# resisitive_pos_servo2.net
KiCad netlist of a schematic drawn in EAGLE
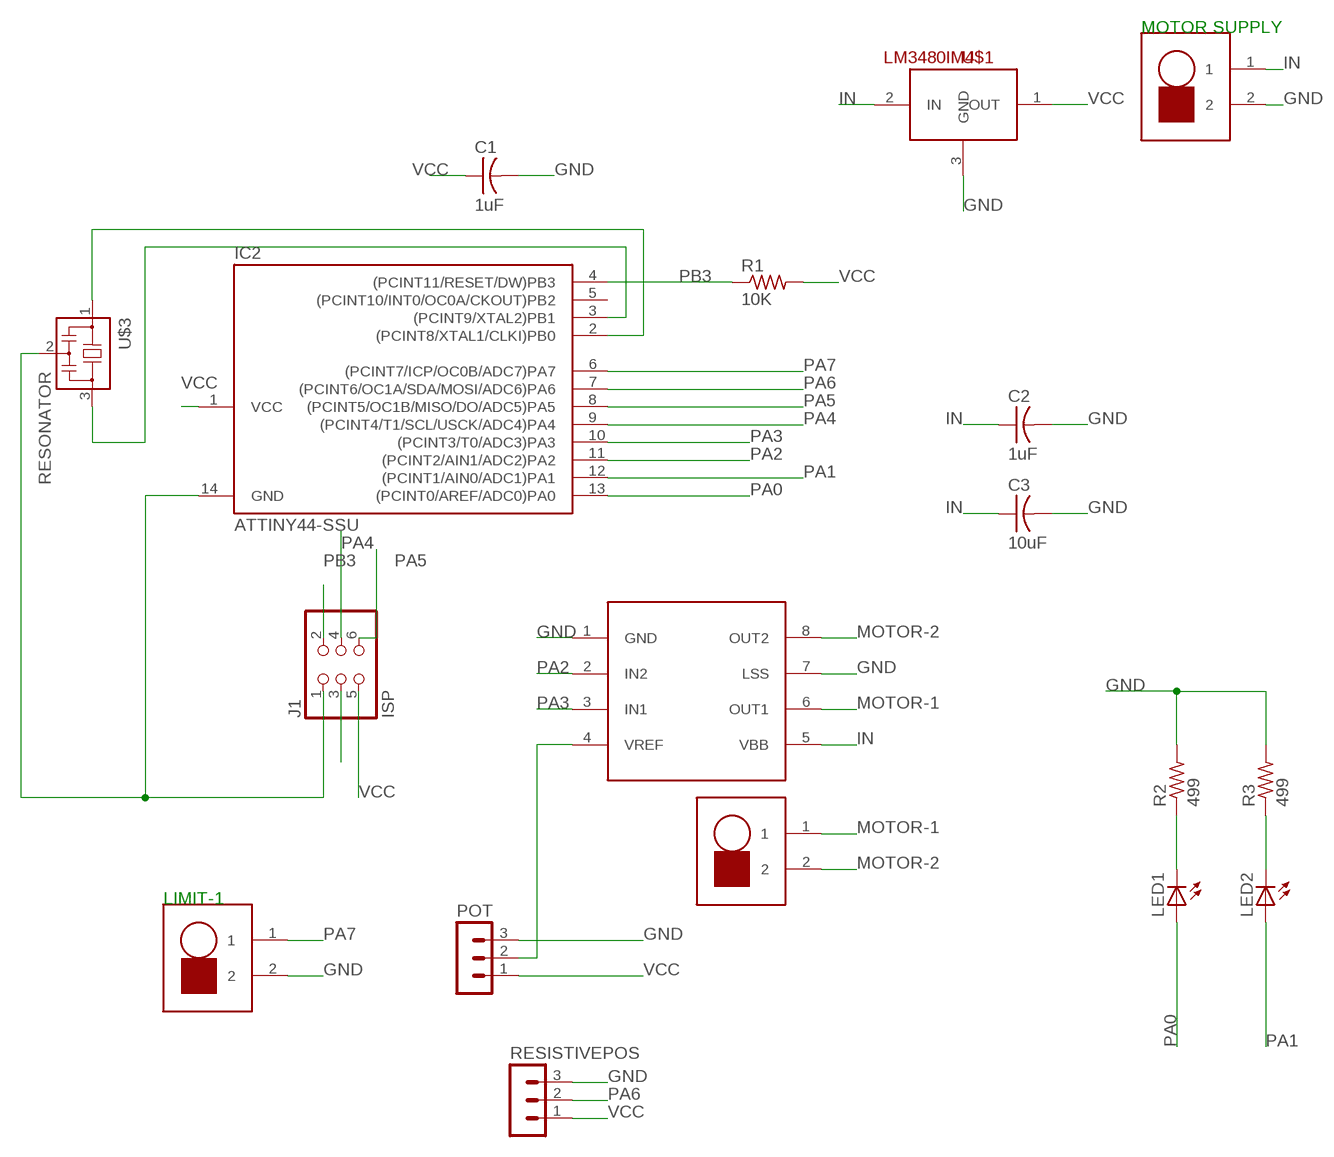
[diagram p0: schematic, sheet 1]

(export (version "E")
  (design (tool "Eeschema 10.0.6"))
  (components
    (comp (ref "C1")
      (value "1uF")
      (footprint "eagle-import:C1206")
      (libsource (lib "eagle-import") (part "CAP-US1206"))
    )
    (comp (ref "C2")
      (value "1uF")
      (footprint "eagle-import:C1206")
      (libsource (lib "eagle-import") (part "CAP-US1206"))
    )
    (comp (ref "C3")
      (value "10uF")
      (footprint "eagle-import:C1206")
      (libsource (lib "eagle-import") (part "CAP-US1206"))
    )
    (comp (ref "IC2")
      (value "ATTINY44-SSU")
      (footprint "eagle-import:SOIC14")
      (libsource (lib "eagle-import") (part "ATTINY44-SSU"))
    )
    (comp (ref "J1")
      (value "ISP")
      (footprint "eagle-import:2X03SMD")
      (libsource (lib "eagle-import") (part "PINHD-2X3-SMD"))
    )
    (comp (ref "LED1")
      (value "LEDSMT1206")
      (footprint "eagle-import:1206")
      (libsource (lib "eagle-import") (part "LEDSMT1206"))
    )
    (comp (ref "LED2")
      (value "LEDSMT1206")
      (footprint "eagle-import:1206")
      (libsource (lib "eagle-import") (part "LEDSMT1206"))
    )
    (comp (ref "MOTOR-SUPPLY")
      (value "3.5MMSCREWTERMINAL2")
      (footprint "eagle-import:SCREWTERMINAL-3.5MM-2-NS")
      (libsource (lib "eagle-import") (part "3.5MMSCREWTERMINAL2"))
    )
    (comp (ref "POT")
      (value "MA03-1")
      (footprint "eagle-import:MA03-1")
      (libsource (lib "eagle-import") (part "MA03-1"))
    )
    (comp (ref "R1")
      (value "10K")
      (footprint "eagle-import:R1206FAB")
      (libsource (lib "eagle-import") (part "RES-US1206FAB"))
    )
    (comp (ref "R2")
      (value "499")
      (footprint "eagle-import:R1206FAB")
      (libsource (lib "eagle-import") (part "RES-US1206FAB"))
    )
    (comp (ref "R3")
      (value "499")
      (footprint "eagle-import:R1206FAB")
      (libsource (lib "eagle-import") (part "RES-US1206FAB"))
    )
    (comp (ref "RESISTIVEPOS")
      (value "MA03-1")
      (footprint "eagle-import:MA03-1")
      (libsource (lib "eagle-import") (part "MA03-1"))
    )
    (comp (ref "U$1")
      (value "LM3480IM4")
      (footprint "eagle-import:SOT23-3")
      (libsource (lib "eagle-import") (part "LM3480IM4"))
    )
    (comp (ref "U$2")
      (value "3.5MMSCREWTERMINAL2")
      (footprint "eagle-import:SCREWTERMINAL-3.5MM-2-NS")
      (libsource (lib "eagle-import") (part "3.5MMSCREWTERMINAL2"))
    )
    (comp (ref "U$3")
      (value "RESONATOR")
      (footprint "eagle-import:EFOBM")
      (libsource (lib "eagle-import") (part "RESONATOR"))
    )
    (comp (ref "U$5")
      (value "3.5MMSCREWTERMINAL2")
      (footprint "eagle-import:SCREWTERMINAL-3.5MM-2-NS")
      (libsource (lib "eagle-import") (part "3.5MMSCREWTERMINAL2"))
    )
    (comp (ref "U$6")
      (value "A4953-H-BRIDGE-MOTOR-DRIVER")
      (footprint "eagle-import:SOIC8")
      (libsource (lib "eagle-import") (part "A4953-H-BRIDGE-MOTOR-DRIVER"))
    )
  )
  (nets
    (net (code "1") (name "/GND") (class "Default")
      (node (ref "C1") (pin "2") (pinfunction "2_2") (pintype "passive"))
      (node (ref "C2") (pin "2") (pinfunction "2_2") (pintype "passive"))
      (node (ref "C3") (pin "2") (pinfunction "2_2") (pintype "passive"))
      (node (ref "IC2") (pin "14") (pinfunction "GND_14") (pintype "power_in"))
      (node (ref "J1") (pin "1") (pinfunction "1_1") (pintype "passive"))
      (node (ref "MOTOR-SUPPLY") (pin "2") (pinfunction "2_2") (pintype "bidirectional"))
      (node (ref "POT") (pin "3") (pinfunction "3_3") (pintype "passive"))
      (node (ref "R2") (pin "2") (pinfunction "2_2") (pintype "passive"))
      (node (ref "R3") (pin "2") (pinfunction "2_2") (pintype "passive"))
      (node (ref "RESISTIVEPOS") (pin "3") (pinfunction "3_3") (pintype "passive"))
      (node (ref "U$1") (pin "3") (pinfunction "GND_3") (pintype "bidirectional"))
      (node (ref "U$3") (pin "2") (pinfunction "2_2") (pintype "passive"))
      (node (ref "U$5") (pin "2") (pinfunction "2_2") (pintype "bidirectional"))
      (node (ref "U$6") (pin "1") (pinfunction "GND_1") (pintype "bidirectional"))
      (node (ref "U$6") (pin "7") (pinfunction "LSS_7") (pintype "bidirectional"))
    )
    (net (code "2") (name "/IN") (class "Default")
      (node (ref "C2") (pin "1") (pinfunction "1_1") (pintype "passive"))
      (node (ref "C3") (pin "1") (pinfunction "1_1") (pintype "passive"))
      (node (ref "MOTOR-SUPPLY") (pin "1") (pinfunction "1_1") (pintype "bidirectional"))
      (node (ref "U$1") (pin "2") (pinfunction "IN_2") (pintype "bidirectional"))
      (node (ref "U$6") (pin "5") (pinfunction "VBB_5") (pintype "bidirectional"))
    )
    (net (code "3") (name "/MOTOR-1") (class "Default")
      (node (ref "U$2") (pin "1") (pinfunction "1_1") (pintype "bidirectional"))
      (node (ref "U$6") (pin "6") (pinfunction "OUT1_6") (pintype "bidirectional"))
    )
    (net (code "4") (name "/MOTOR-2") (class "Default")
      (node (ref "U$2") (pin "2") (pinfunction "2_2") (pintype "bidirectional"))
      (node (ref "U$6") (pin "8") (pinfunction "OUT2_8") (pintype "bidirectional"))
    )
    (net (code "5") (name "/PA0") (class "Default")
      (node (ref "IC2") (pin "13") (pinfunction "(PCINT0/AREF/ADC0)PA0_13") (pintype "bidirectional"))
      (node (ref "LED1") (pin "A") (pinfunction "A_A") (pintype "passive"))
    )
    (net (code "6") (name "/PA1") (class "Default")
      (node (ref "IC2") (pin "12") (pinfunction "(PCINT1/AIN0/ADC1)PA1_12") (pintype "bidirectional"))
      (node (ref "LED2") (pin "A") (pinfunction "A_A") (pintype "passive"))
    )
    (net (code "7") (name "/PA2") (class "Default")
      (node (ref "IC2") (pin "11") (pinfunction "(PCINT2/AIN1/ADC2)PA2_11") (pintype "bidirectional"))
      (node (ref "U$6") (pin "2") (pinfunction "IN2_2") (pintype "bidirectional"))
    )
    (net (code "8") (name "/PA3") (class "Default")
      (node (ref "IC2") (pin "10") (pinfunction "(PCINT3/T0/ADC3)PA3_10") (pintype "bidirectional"))
      (node (ref "U$6") (pin "3") (pinfunction "IN1_3") (pintype "bidirectional"))
    )
    (net (code "9") (name "/PA4") (class "Default")
      (node (ref "IC2") (pin "9") (pinfunction "(PCINT4/T1/SCL/USCK/ADC4)PA4_9") (pintype "bidirectional"))
      (node (ref "J1") (pin "4") (pinfunction "4_4") (pintype "passive"))
    )
    (net (code "10") (name "/PA5") (class "Default")
      (node (ref "IC2") (pin "8") (pinfunction "(PCINT5/OC1B/MISO/DO/ADC5)PA5_8") (pintype "bidirectional"))
      (node (ref "J1") (pin "6") (pinfunction "6_6") (pintype "passive"))
    )
    (net (code "11") (name "/PA6") (class "Default")
      (node (ref "IC2") (pin "7") (pinfunction "(PCINT6/OC1A/SDA/MOSI/ADC6)PA6_7") (pintype "bidirectional"))
      (node (ref "J1") (pin "3") (pinfunction "3_3") (pintype "passive"))
      (node (ref "RESISTIVEPOS") (pin "2") (pinfunction "2_2") (pintype "passive"))
    )
    (net (code "12") (name "/PA7") (class "Default")
      (node (ref "IC2") (pin "6") (pinfunction "(PCINT7/ICP/OC0B/ADC7)PA7_6") (pintype "bidirectional"))
      (node (ref "U$5") (pin "1") (pinfunction "1_1") (pintype "bidirectional"))
    )
    (net (code "13") (name "/PB3") (class "Default")
      (node (ref "IC2") (pin "4") (pinfunction "(PCINT11/RESET/DW)PB3_4") (pintype "bidirectional"))
      (node (ref "J1") (pin "2") (pinfunction "2_2") (pintype "passive"))
      (node (ref "R1") (pin "1") (pinfunction "1_1") (pintype "passive"))
    )
    (net (code "14") (name "/VCC") (class "Default")
      (node (ref "C1") (pin "1") (pinfunction "1_1") (pintype "passive"))
      (node (ref "IC2") (pin "1") (pinfunction "VCC_1") (pintype "power_in"))
      (node (ref "J1") (pin "5") (pinfunction "5_5") (pintype "passive"))
      (node (ref "POT") (pin "1") (pinfunction "1_1") (pintype "passive"))
      (node (ref "R1") (pin "2") (pinfunction "2_2") (pintype "passive"))
      (node (ref "RESISTIVEPOS") (pin "1") (pinfunction "1_1") (pintype "passive"))
      (node (ref "U$1") (pin "1") (pinfunction "OUT_1") (pintype "bidirectional"))
    )
    (net (code "15") (name "Net-(IC2-(PCINT8{slash}XTAL1{slash}CLKI)PB0)") (class "Default")
      (node (ref "IC2") (pin "2") (pinfunction "(PCINT8/XTAL1/CLKI)PB0_2") (pintype "bidirectional"))
      (node (ref "U$3") (pin "1") (pinfunction "1_1") (pintype "passive"))
    )
    (net (code "16") (name "Net-(IC2-(PCINT9{slash}XTAL2)PB1)") (class "Default")
      (node (ref "IC2") (pin "3") (pinfunction "(PCINT9/XTAL2)PB1_3") (pintype "bidirectional"))
      (node (ref "U$3") (pin "3") (pinfunction "3_3") (pintype "passive"))
    )
    (net (code "17") (name "Net-(LED1-PadC)") (class "Default")
      (node (ref "LED1") (pin "C") (pinfunction "C_C") (pintype "passive"))
      (node (ref "R2") (pin "1") (pinfunction "1_1") (pintype "passive"))
    )
    (net (code "18") (name "Net-(LED2-PadC)") (class "Default")
      (node (ref "LED2") (pin "C") (pinfunction "C_C") (pintype "passive"))
      (node (ref "R3") (pin "1") (pinfunction "1_1") (pintype "passive"))
    )
    (net (code "19") (name "Net-(U$6-VREF)") (class "Default")
      (node (ref "POT") (pin "2") (pinfunction "2_2") (pintype "passive"))
      (node (ref "U$6") (pin "4") (pinfunction "VREF_4") (pintype "bidirectional"))
    )
    (net (code "20") (name "unconnected-(IC2-(PCINT10{slash}INT0{slash}OC0A{slash}CKOUT)PB2-Pad5)") (class "Default")
      (node (ref "IC2") (pin "5") (pinfunction "(PCINT10/INT0/OC0A/CKOUT)PB2_5") (pintype "bidirectional"))
    )
  )
)
